# SolderingStation_Processor.net
KiCad netlist of a schematic drawn in Altium Designer
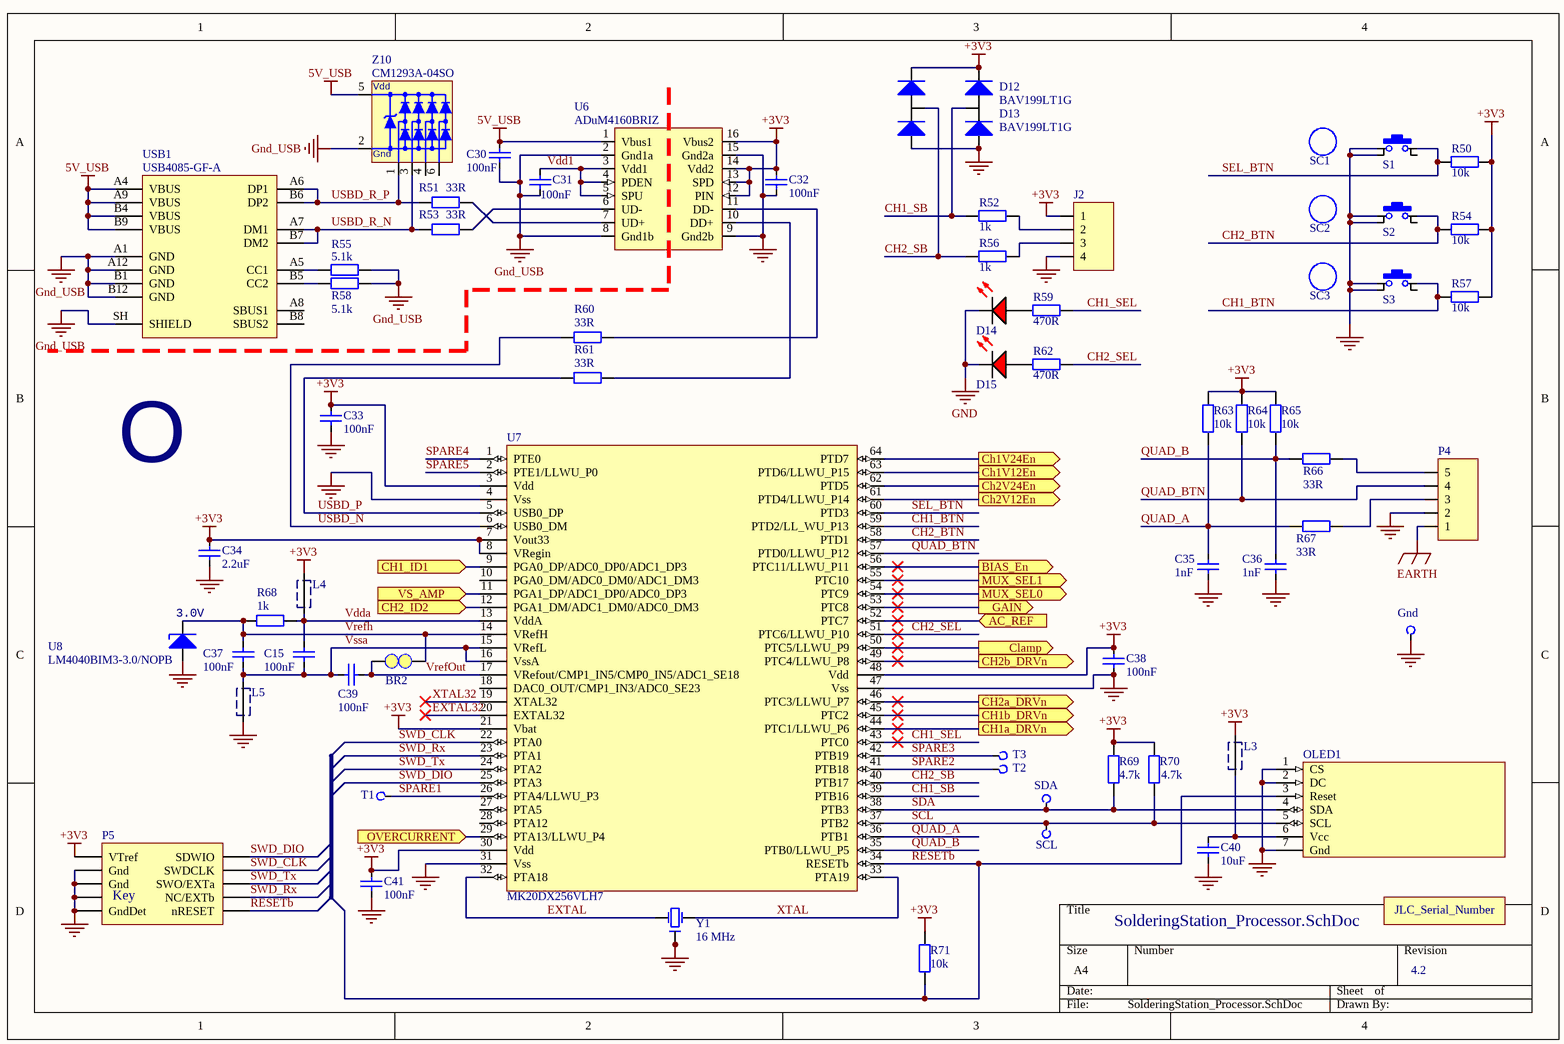
[diagram p0: SolderingStation_Processor.SchDoc]

(export (version "E")
  (design (tool "Eeschema 10.0.6"))
  (components
    (comp (ref "BR2")
      (value "Solder Bridge (Open)")
      (footprint "SolderBridge(Open)")
      (description "Solder bridge")
      (libsource (lib "MyLibrary") (part "SolderBridge(Open)"))
    )
    (comp (ref "C15")
      (value "100nF")
      (footprint "CCNP1608-0603_N")
      (description "Capacitor non-polar SMT 0603")
      (fields
        (field (name "MANUFACTURER") "Generic Components")
        (field (name "PUBLISHER") "Altium Hobart Technology Centre")
      )
      (libsource (lib "MyLibrary") (part "Cap_CCNP_0603_100nF"))
    )
    (comp (ref "C30")
      (value "100nF")
      (footprint "CCNP1608-0603_N")
      (description "Capacitor non-polar SMT 0603")
      (fields
        (field (name "MANUFACTURER") "Generic Components")
        (field (name "PUBLISHER") "Altium Hobart Technology Centre")
      )
      (libsource (lib "MyLibrary") (part "Cap_CCNP_0603_100nF"))
    )
    (comp (ref "C31")
      (value "100nF")
      (footprint "CCNP1608-0603_N")
      (description "Capacitor non-polar SMT 0603")
      (fields
        (field (name "MANUFACTURER") "Generic Components")
        (field (name "PUBLISHER") "Altium Hobart Technology Centre")
      )
      (libsource (lib "MyLibrary") (part "Cap_CCNP_0603_100nF"))
    )
    (comp (ref "C32")
      (value "100nF")
      (footprint "CCNP1608-0603_N")
      (description "Capacitor non-polar SMT 0603")
      (fields
        (field (name "MANUFACTURER") "Generic Components")
        (field (name "PUBLISHER") "Altium Hobart Technology Centre")
      )
      (libsource (lib "MyLibrary") (part "Cap_CCNP_0603_100nF"))
    )
    (comp (ref "C33")
      (value "100nF")
      (footprint "CCNP1608-0603_N")
      (description "Capacitor non-polar SMT 0603")
      (fields
        (field (name "MANUFACTURER") "Generic Components")
        (field (name "PUBLISHER") "Altium Hobart Technology Centre")
      )
      (libsource (lib "MyLibrary") (part "Cap_CCNP_0603_100nF"))
    )
    (comp (ref "C34")
      (value "2.2uF")
      (footprint "CCNP1608-0603_N")
      (description "Capacitor non-polar SMT 0603")
      (fields
        (field (name "MANUFACTURER") "Generic Components")
        (field (name "PUBLISHER") "Altium Hobart Technology Centre")
      )
      (libsource (lib "MyLibrary") (part "Cap_CCNP_0603_2u2F"))
    )
    (comp (ref "C35")
      (value "1nF")
      (footprint "CCNP1608-0603_N")
      (description "Capacitor non-polar SMT 0603")
      (fields
        (field (name "MANUFACTURER") "Generic Components")
        (field (name "PUBLISHER") "Altium Hobart Technology Centre")
      )
      (libsource (lib "MyLibrary") (part "Cap_CCNP_0603_1nF"))
    )
    (comp (ref "C36")
      (value "1nF")
      (footprint "CCNP1608-0603_N")
      (description "Capacitor non-polar SMT 0603")
      (fields
        (field (name "MANUFACTURER") "Generic Components")
        (field (name "PUBLISHER") "Altium Hobart Technology Centre")
      )
      (libsource (lib "MyLibrary") (part "Cap_CCNP_0603_1nF"))
    )
    (comp (ref "C37")
      (value "100nF")
      (footprint "CCNP1608-0603_N")
      (description "Capacitor non-polar SMT 0603")
      (fields
        (field (name "MANUFACTURER") "Generic Components")
        (field (name "PUBLISHER") "Altium Hobart Technology Centre")
      )
      (libsource (lib "MyLibrary") (part "Cap_CCNP_0603_100nF"))
    )
    (comp (ref "C38")
      (value "100nF")
      (footprint "CCNP1608-0603_N")
      (description "Capacitor non-polar SMT 0603")
      (fields
        (field (name "MANUFACTURER") "Generic Components")
        (field (name "PUBLISHER") "Altium Hobart Technology Centre")
      )
      (libsource (lib "MyLibrary") (part "Cap_CCNP_0603_100nF"))
    )
    (comp (ref "C39")
      (value "100nF")
      (footprint "CCNP1608-0603_N")
      (description "Capacitor non-polar SMT 0603")
      (fields
        (field (name "MANUFACTURER") "Generic Components")
        (field (name "PUBLISHER") "Altium Hobart Technology Centre")
      )
      (libsource (lib "MyLibrary") (part "Cap_CCNP_0603_100nF"))
    )
    (comp (ref "C40")
      (value "10uF")
      (footprint "CCNP2012-0805")
      (description "Capacitor non-polar SMT 0805")
      (fields
        (field (name "MANUFACTURER") "Generic Components")
        (field (name "PUBLISHER") "Altium Hobart Technology Centre")
      )
      (libsource (lib "MyLibrary") (part "Cap_CCNP_0805_10uF"))
    )
    (comp (ref "C41")
      (value "100nF")
      (footprint "CCNP1608-0603_N")
      (description "Capacitor non-polar SMT 0603")
      (fields
        (field (name "MANUFACTURER") "Generic Components")
        (field (name "PUBLISHER") "Altium Hobart Technology Centre")
      )
      (libsource (lib "MyLibrary") (part "Cap_CCNP_0603_100nF"))
    )
    (comp (ref "D12")
      (value "BAV199LT1G")
      (footprint "SOT23_M")
      (description "Dual Series low-leakage switching diodes, 3-Pin SOT-23")
      (libsource (lib "MySchLib") (part "BAV199LT1G"))
    )
    (comp (ref "D13")
      (value "BAV199LT1G")
      (footprint "SOT23_M")
      (description "Dual Series low-leakage switching diodes, 3-Pin SOT-23")
      (libsource (lib "MySchLib") (part "BAV199LT1G"))
    )
    (comp (ref "D14")
      (value "LED")
      (footprint "LED3MM-RED - 10mm Proud")
      (description "3mm Red LED")
      (fields (field (name "MANUFACTURER") "Generic Components") (field (name "PUBLISHER") "Altium Limited"))
      (libsource (lib "MySchLib") (part "LED_3MM_RED"))
    )
    (comp (ref "D15")
      (value "LED")
      (footprint "LED3MM-RED - 10mm Proud")
      (description "3mm Red LED")
      (fields (field (name "MANUFACTURER") "Generic Components") (field (name "PUBLISHER") "Altium Limited"))
      (libsource (lib "MySchLib") (part "LED_3MM_RED"))
    )
    (comp (ref "Gnd")
      (value "Gnd")
      (footprint "PCBPIN - 0.9mm")
      (description "Test Point")
      (libsource (lib "MySchLib") (part "TP"))
    )
    (comp (ref "J2")
      (value "JST XH Connector, 4-Pin")
      (footprint "jst-b4b-xh-ax")
      (fields (field (name "PUBLISHER") "Altium Limited"))
      (libsource (lib "MyLibrary") (part "JST-B4B-XH-A"))
    )
    (comp (ref "JLC_Serial_Number1")
      (value "JLC_Serial_Number")
      (footprint "JLC_Serial_Number")
      (libsource (lib "MyLibrary") (part "JLC_Serial_Number"))
    )
    (comp (ref "L3")
      (value "Ferrite Bead 600R@100MHz")
      (footprint "FB2012-0805")
      (description "Ferrite Bead 600Ω @ 100MHz 1 500mA 300mΩ 0805")
      (libsource (lib "MySchLib") (part "Ferrite Bead 0805 600R"))
    )
    (comp (ref "L4")
      (value "Ferrite Bead 600R@100MHz")
      (footprint "FB1608-0603")
      (description "Ferrite Bead 600Ω @ 100MHz 1 200mA 450mΩ 0603")
      (libsource (lib "MySchLib") (part "Ferrite Bead 0603 600R"))
    )
    (comp (ref "L5")
      (value "Ferrite Bead 600R@100MHz")
      (footprint "FB1608-0603")
      (description "Ferrite Bead 600Ω @ 100MHz 1 200mA 450mΩ 0603")
      (libsource (lib "MySchLib") (part "Ferrite Bead 0603 600R"))
    )
    (comp (ref "Logo1")
      (value "OSHW Logo")
      (footprint "OSHW")
      (libsource (lib "MyLibrary") (part "OSHW Logo"))
    )
    (comp (ref "OLED1")
      (value "OLED_Display")
      (footprint "OLED_Display_128x64_2.4inch - no mounting holes")
      (description "OLED Display 128x64 pixels, 2.4inch")
      (libsource (lib "MySchLib") (part "OLED_Display_128x64_2.4inch"))
    )
    (comp (ref "P4")
      (value "Header, 5-Pin")
      (footprint "HDR1X5S")
      (fields (field (name "PUBLISHER") "Altium Limited"))
      (libsource (lib "MyLibrary") (part "Header 1x5"))
    )
    (comp (ref "P5")
      (value "SWD Connector 2x5-Pin")
      (footprint "SWD-2x5-Jig-Header")
      (fields (field (name "PUBLISHER") "Altium Limited"))
      (libsource (lib "MySchLib") (part "SWD2X5_JIG"))
    )
    (comp (ref "R50")
      (value "10k")
      (footprint "CR1608-0603_N")
      (description "Resistor SMT 0603")
      (fields
        (field (name "MANUFACTURER") "Generic Components")
        (field (name "PUBLISHER") "Altium Hobart Technology Centre")
      )
      (libsource (lib "MyLibrary") (part "Res_CR0603_10k"))
    )
    (comp (ref "R51")
      (value "33R")
      (footprint "CR1608-0603_N")
      (description "Resistor SMT 0603")
      (fields
        (field (name "MANUFACTURER") "Generic Components")
        (field (name "PUBLISHER") "Altium Hobart Technology Centre")
      )
      (libsource (lib "MyLibrary") (part "Res_CR0603_33R"))
    )
    (comp (ref "R52")
      (value "1k")
      (footprint "CR1608-0603_N")
      (description "Resistor SMT 0603")
      (fields
        (field (name "MANUFACTURER") "Generic Components")
        (field (name "PUBLISHER") "Altium Hobart Technology Centre")
      )
      (libsource (lib "") (part "Res_CR0603_1k_1"))
    )
    (comp (ref "R53")
      (value "33R")
      (footprint "CR1608-0603_N")
      (description "Resistor SMT 0603")
      (fields
        (field (name "MANUFACTURER") "Generic Components")
        (field (name "PUBLISHER") "Altium Hobart Technology Centre")
      )
      (libsource (lib "MyLibrary") (part "Res_CR0603_33R"))
    )
    (comp (ref "R54")
      (value "10k")
      (footprint "CR1608-0603_N")
      (description "Resistor SMT 0603")
      (fields
        (field (name "MANUFACTURER") "Generic Components")
        (field (name "PUBLISHER") "Altium Hobart Technology Centre")
      )
      (libsource (lib "MyLibrary") (part "Res_CR0603_10k"))
    )
    (comp (ref "R55")
      (value "5.1k")
      (footprint "CR1608-0603_N")
      (description "Resistor SMT 0603")
      (fields
        (field (name "MANUFACTURER") "Generic Components")
        (field (name "PUBLISHER") "Altium Hobart Technology Centre")
      )
      (libsource (lib "MyLibrary") (part "Res_CR0603_5k1"))
    )
    (comp (ref "R56")
      (value "1k")
      (footprint "CR1608-0603_N")
      (description "Resistor SMT 0603")
      (fields
        (field (name "MANUFACTURER") "Generic Components")
        (field (name "PUBLISHER") "Altium Hobart Technology Centre")
      )
      (libsource (lib "") (part "Res_CR0603_1k_1"))
    )
    (comp (ref "R57")
      (value "10k")
      (footprint "CR1608-0603_N")
      (description "Resistor SMT 0603")
      (fields
        (field (name "MANUFACTURER") "Generic Components")
        (field (name "PUBLISHER") "Altium Hobart Technology Centre")
      )
      (libsource (lib "MyLibrary") (part "Res_CR0603_10k"))
    )
    (comp (ref "R58")
      (value "5.1k")
      (footprint "CR1608-0603_N")
      (description "Resistor SMT 0603")
      (fields
        (field (name "MANUFACTURER") "Generic Components")
        (field (name "PUBLISHER") "Altium Hobart Technology Centre")
      )
      (libsource (lib "MyLibrary") (part "Res_CR0603_5k1"))
    )
    (comp (ref "R59")
      (value "470R")
      (footprint "CR1608-0603_N")
      (description "Resistor SMT 0603")
      (fields
        (field (name "MANUFACTURER") "Generic Components")
        (field (name "PUBLISHER") "Altium Hobart Technology Centre")
      )
      (libsource (lib "MyLibrary") (part "Res_CR0603_470R"))
    )
    (comp (ref "R60")
      (value "33R")
      (footprint "CR1608-0603_N")
      (description "Resistor SMT 0603")
      (fields
        (field (name "MANUFACTURER") "Generic Components")
        (field (name "PUBLISHER") "Altium Hobart Technology Centre")
      )
      (libsource (lib "MyLibrary") (part "Res_CR0603_33R"))
    )
    (comp (ref "R61")
      (value "33R")
      (footprint "CR1608-0603_N")
      (description "Resistor SMT 0603")
      (fields
        (field (name "MANUFACTURER") "Generic Components")
        (field (name "PUBLISHER") "Altium Hobart Technology Centre")
      )
      (libsource (lib "MyLibrary") (part "Res_CR0603_33R"))
    )
    (comp (ref "R62")
      (value "470R")
      (footprint "CR1608-0603_N")
      (description "Resistor SMT 0603")
      (fields
        (field (name "MANUFACTURER") "Generic Components")
        (field (name "PUBLISHER") "Altium Hobart Technology Centre")
      )
      (libsource (lib "") (part "Res_CR0603_470R_1"))
    )
    (comp (ref "R63")
      (value "10k")
      (footprint "CR1608-0603_N")
      (description "Resistor SMT 0603")
      (fields
        (field (name "MANUFACTURER") "Generic Components")
        (field (name "PUBLISHER") "Altium Hobart Technology Centre")
      )
      (libsource (lib "") (part "Res_CR0603_10k_1"))
    )
    (comp (ref "R64")
      (value "10k")
      (footprint "CR1608-0603_N")
      (description "Resistor SMT 0603")
      (fields
        (field (name "MANUFACTURER") "Generic Components")
        (field (name "PUBLISHER") "Altium Hobart Technology Centre")
      )
      (libsource (lib "") (part "Res_CR0603_10k_1"))
    )
    (comp (ref "R65")
      (value "10k")
      (footprint "CR1608-0603_N")
      (description "Resistor SMT 0603")
      (fields
        (field (name "MANUFACTURER") "Generic Components")
        (field (name "PUBLISHER") "Altium Hobart Technology Centre")
      )
      (libsource (lib "") (part "Res_CR0603_10k_1"))
    )
    (comp (ref "R66")
      (value "33R")
      (footprint "CR1608-0603_N")
      (description "Resistor SMT 0603")
      (fields
        (field (name "MANUFACTURER") "Generic Components")
        (field (name "PUBLISHER") "Altium Hobart Technology Centre")
      )
      (libsource (lib "MyLibrary") (part "Res_CR0603_33R"))
    )
    (comp (ref "R67")
      (value "33R")
      (footprint "CR1608-0603_N")
      (description "Resistor SMT 0603")
      (fields
        (field (name "MANUFACTURER") "Generic Components")
        (field (name "PUBLISHER") "Altium Hobart Technology Centre")
      )
      (libsource (lib "MyLibrary") (part "Res_CR0603_33R"))
    )
    (comp (ref "R68")
      (value "1k")
      (footprint "CR1608-0603_N")
      (description "Resistor SMT 0603")
      (fields
        (field (name "MANUFACTURER") "Generic Components")
        (field (name "PUBLISHER") "Altium Hobart Technology Centre")
      )
      (libsource (lib "MyLibrary") (part "Res_CR0603_1k"))
    )
    (comp (ref "R69")
      (value "4.7k")
      (footprint "CR1608-0603_N")
      (description "Resistor SMT 0603")
      (fields
        (field (name "MANUFACTURER") "Generic Components")
        (field (name "PUBLISHER") "Altium Hobart Technology Centre")
      )
      (libsource (lib "MyLibrary") (part "Res_CR0603_4k7"))
    )
    (comp (ref "R70")
      (value "4.7k")
      (footprint "CR1608-0603_N")
      (description "Resistor SMT 0603")
      (fields
        (field (name "MANUFACTURER") "Generic Components")
        (field (name "PUBLISHER") "Altium Hobart Technology Centre")
      )
      (libsource (lib "MyLibrary") (part "Res_CR0603_4k7"))
    )
    (comp (ref "R71")
      (value "10k")
      (footprint "CR1608-0603_N")
      (description "Resistor SMT 0603")
      (fields
        (field (name "MANUFACTURER") "Generic Components")
        (field (name "PUBLISHER") "Altium Hobart Technology Centre")
      )
      (libsource (lib "") (part "Res_CR0603_10k_1"))
    )
    (comp (ref "S1")
      (value "SW_PB-B3F1052")
      (footprint "SW_MIN_PB-B3F1052")
      (description "Switch miniature push-button")
      (fields (field (name "MANUFACTURER") "Generic Components") (field (name "PUBLISHER") "Altium Limited"))
      (libsource (lib "MySchLib") (part "SW_PB-B3F1052"))
    )
    (comp (ref "S2")
      (value "SW_PB-B3F1052")
      (footprint "SW_MIN_PB-B3F1052")
      (description "Switch miniature push-button")
      (fields (field (name "MANUFACTURER") "Generic Components") (field (name "PUBLISHER") "Altium Limited"))
      (libsource (lib "MySchLib") (part "SW_PB-B3F1052"))
    )
    (comp (ref "S3")
      (value "SW_PB-B3F1052")
      (footprint "SW_MIN_PB-B3F1052")
      (description "Switch miniature push-button")
      (fields (field (name "MANUFACTURER") "Generic Components") (field (name "PUBLISHER") "Altium Limited"))
      (libsource (lib "MySchLib") (part "SW_PB-B3F1052"))
    )
    (comp (ref "SC1")
      (value "B32-2010")
      (footprint "SW-CAP-B32-2010")
      (description "Switch Cap")
      (libsource (lib "MySchLib") (part "Switch-Cap - B32-2010"))
    )
    (comp (ref "SC2")
      (value "B32-2010")
      (footprint "SW-CAP-B32-2010")
      (description "Switch Cap")
      (libsource (lib "MySchLib") (part "Switch-Cap - B32-2010"))
    )
    (comp (ref "SC3")
      (value "B32-2010")
      (footprint "SW-CAP-B32-2010")
      (description "Switch Cap")
      (libsource (lib "MySchLib") (part "Switch-Cap - B32-2010"))
    )
    (comp (ref "SCL")
      (value "SCL")
      (footprint "PCBPIN - 0.9mm")
      (description "Test Point")
      (libsource (lib "MySchLib") (part "TP"))
    )
    (comp (ref "SDA")
      (value "SDA")
      (footprint "PCBPIN - 0.9mm")
      (description "Test Point")
      (libsource (lib "MySchLib") (part "TP"))
    )
    (comp (ref "T1")
      (value "PTA4")
      (footprint "PCBPIN - 0.9mm")
      (description "Test Point")
      (libsource (lib "MySchLib") (part "TP"))
    )
    (comp (ref "T2")
      (value "PTB18")
      (footprint "PCBPIN - 0.9mm")
      (description "Test Point")
      (libsource (lib "MySchLib") (part "TP"))
    )
    (comp (ref "T3")
      (value "PTB19")
      (footprint "PCBPIN - 0.9mm")
      (description "Test Point")
      (libsource (lib "MySchLib") (part "TP"))
    )
    (comp (ref "U6")
      (value "ADuM4160BRIZ")
      (footprint "SOIC127P1030-16M")
      (description "Full/Low Speed 5 kV USB Digital Isolator")
      (libsource (lib "MySchLib") (part "ADuM4160BRIZ"))
    )
    (comp (ref "U7")
      (value "MK20DX256VLH7")
      (footprint "TSQFP50P1200X1200-64M")
      (description "Arm Cortex M4\r\nApplies to MK20DX64VLH7, MK20DX128VLH7, MK20DX256VLH7")
      (libsource (lib "MyLibrary") (part "MK20DX256VLH7"))
    )
    (comp (ref "U8")
      (value "LM4040BIM3-3.0/NOPB")
      (footprint "SOT23_M")
      (description "IC 2.5V VREF SHUNT 0.2% SOT23-3")
      (libsource (lib "MySchLib") (part "LM4040BIM3-2.5/NOPB"))
    )
    (comp (ref "USB1")
      (value "USB4085-GF-A")
      (footprint "USB4085-GF-A")
      (description "USB-C, USB 2.0 Receptacle Connector 16 Position Through Hole, Right Angle")
      (fields (field (name "DIGIKEY PART NUMBER") "2073-USB4085-GF-ACT-ND"))
      (libsource (lib "MyLibrary") (part "USB4085-GF-A"))
    )
    (comp (ref "Y1")
      (value "16 MHz")
      (footprint "Crystal_SMD_3.2x2.5")
      (description "Crystal SMD 3.2 x 2.5 x 0.7 mm")
      (fields
        (field (name "MANUFACTURER") "Generic Components")
        (field (name "PUBLISHER") "Altium Hobart Technology Centre")
      )
      (libsource (lib "MyLibrary") (part "Crystal 16MHz"))
    )
    (comp (ref "Z10")
      (value "CM1293A-04SO")
      (footprint "SOT457_M - 180")
      (description "Ultra low capacitance quadruple rail-to-rail ESD protection")
      (libsource (lib "MySchLib") (part "CM1293A-04SO"))
    )
  )
  (nets
    (net (code "1") (name "+3V3") (class "Default")
      (node (ref "C32") (pin "2") (pinfunction "2_2") (pintype "passive"))
      (node (ref "C33") (pin "2") (pinfunction "2_2") (pintype "passive"))
      (node (ref "C34") (pin "2") (pinfunction "2_2") (pintype "passive"))
      (node (ref "C38") (pin "2") (pinfunction "2_2") (pintype "passive"))
      (node (ref "C41") (pin "2") (pinfunction "2_2") (pintype "passive"))
      (node (ref "D12") (pin "2") (pinfunction "A2_2") (pintype "passive"))
      (node (ref "D13") (pin "2") (pinfunction "A2_2") (pintype "passive"))
      (node (ref "J2") (pin "1") (pinfunction "1_1") (pintype "passive"))
      (node (ref "L3") (pin "1") (pinfunction "1_1") (pintype "passive"))
      (node (ref "L4") (pin "2") (pinfunction "2_2") (pintype "passive"))
      (node (ref "P5") (pin "1") (pinfunction "VTref_1") (pintype "passive"))
      (node (ref "R50") (pin "2") (pinfunction "2_2") (pintype "passive"))
      (node (ref "R54") (pin "2") (pinfunction "2_2") (pintype "passive"))
      (node (ref "R57") (pin "2") (pinfunction "2_2") (pintype "passive"))
      (node (ref "R63") (pin "2") (pinfunction "2_2") (pintype "passive"))
      (node (ref "R64") (pin "2") (pinfunction "2_2") (pintype "passive"))
      (node (ref "R65") (pin "2") (pinfunction "2_2") (pintype "passive"))
      (node (ref "R69") (pin "2") (pinfunction "2_2") (pintype "passive"))
      (node (ref "R70") (pin "2") (pinfunction "2_2") (pintype "passive"))
      (node (ref "R71") (pin "2") (pinfunction "2_2") (pintype "passive"))
      (node (ref "U6") (pin "12") (pinfunction "PIN_12") (pintype "input"))
      (node (ref "U6") (pin "13") (pinfunction "SPD_13") (pintype "input"))
      (node (ref "U6") (pin "14") (pinfunction "Vdd2_14") (pintype "power_in"))
      (node (ref "U6") (pin "16") (pinfunction "Vbus2_16") (pintype "power_in"))
      (node (ref "U7") (pin "21") (pinfunction "Vbat_21") (pintype "passive"))
      (node (ref "U7") (pin "3") (pinfunction "Vdd_3") (pintype "power_in"))
      (node (ref "U7") (pin "30") (pinfunction "Vdd_30") (pintype "power_in"))
      (node (ref "U7") (pin "48") (pinfunction "Vdd_48") (pintype "power_in"))
      (node (ref "U7") (pin "7") (pinfunction "Vout33_7") (pintype "power_in"))
      (node (ref "U7") (pin "8") (pinfunction "VRegin_8") (pintype "passive"))
    )
    (net (code "2") (name "/AC_REF") (class "Default")
      (node (ref "U7") (pin "52") (pinfunction "PTC7_52") (pintype "bidirectional"))
    )
    (net (code "3") (name "/BIAS_En") (class "Default")
      (node (ref "U7") (pin "56") (pinfunction "PTC11/LLWU_P11_56") (pintype "bidirectional"))
    )
    (net (code "4") (name "/CH1_BTN") (class "Default")
      (node (ref "R57") (pin "1") (pinfunction "1_1") (pintype "passive"))
      (node (ref "S3") (pin "2") (pinfunction "2_2") (pintype "passive"))
      (node (ref "U7") (pin "59") (pinfunction "PTD2/LL_WU_P13_59") (pintype "bidirectional"))
    )
    (net (code "5") (name "/CH1_ID1") (class "Default")
      (node (ref "U7") (pin "9") (pinfunction "PGA0_DP/ADC0_DP0/ADC1_DP3_9") (pintype "passive"))
    )
    (net (code "6") (name "/CH1_SB") (class "Default")
      (node (ref "D13") (pin "3") (pinfunction "K_3") (pintype "passive"))
      (node (ref "R52") (pin "1") (pinfunction "1_1") (pintype "passive"))
      (node (ref "U7") (pin "39") (pinfunction "PTB16_39") (pintype "bidirectional"))
    )
    (net (code "7") (name "/CH1_SEL") (class "Default")
      (node (ref "R59") (pin "1") (pinfunction "1_1") (pintype "passive"))
      (node (ref "U7") (pin "43") (pinfunction "PTC0_43") (pintype "bidirectional"))
    )
    (net (code "8") (name "/CH1a_DRVn") (class "Default")
      (node (ref "U7") (pin "44") (pinfunction "PTC1/LLWU_P6_44") (pintype "bidirectional"))
    )
    (net (code "9") (name "/CH1b_DRVn") (class "Default")
      (node (ref "U7") (pin "45") (pinfunction "PTC2_45") (pintype "bidirectional"))
    )
    (net (code "10") (name "/CH2_BTN") (class "Default")
      (node (ref "R54") (pin "1") (pinfunction "1_1") (pintype "passive"))
      (node (ref "S2") (pin "2") (pinfunction "2_2") (pintype "passive"))
      (node (ref "U7") (pin "58") (pinfunction "PTD1_58") (pintype "bidirectional"))
    )
    (net (code "11") (name "/CH2_ID2") (class "Default")
      (node (ref "U7") (pin "12") (pinfunction "PGA1_DM/ADC1_DM0/ADC0_DM3_12") (pintype "passive"))
    )
    (net (code "12") (name "/CH2_SB") (class "Default")
      (node (ref "D12") (pin "3") (pinfunction "K_3") (pintype "passive"))
      (node (ref "R56") (pin "1") (pinfunction "1_1") (pintype "passive"))
      (node (ref "U7") (pin "40") (pinfunction "PTB17_40") (pintype "bidirectional"))
    )
    (net (code "13") (name "/CH2_SEL") (class "Default")
      (node (ref "R62") (pin "2") (pinfunction "2_2") (pintype "passive"))
      (node (ref "U7") (pin "51") (pinfunction "PTC6/LLWU_P10_51") (pintype "bidirectional"))
    )
    (net (code "14") (name "/CH2a_DRVn") (class "Default")
      (node (ref "U7") (pin "46") (pinfunction "PTC3/LLWU_P7_46") (pintype "bidirectional"))
    )
    (net (code "15") (name "/CH2b_DRVn") (class "Default")
      (node (ref "U7") (pin "49") (pinfunction "PTC4/LLWU_P8_49") (pintype "bidirectional"))
    )
    (net (code "16") (name "/Ch1V12En") (class "Default")
      (node (ref "U7") (pin "63") (pinfunction "PTD6/LLWU_P15_63") (pintype "bidirectional"))
    )
    (net (code "17") (name "/Ch1V24En") (class "Default")
      (node (ref "U7") (pin "64") (pinfunction "PTD7_64") (pintype "bidirectional"))
    )
    (net (code "18") (name "/Ch2V12En") (class "Default")
      (node (ref "U7") (pin "61") (pinfunction "PTD4/LLWU_P14_61") (pintype "bidirectional"))
    )
    (net (code "19") (name "/Ch2V24En") (class "Default")
      (node (ref "U7") (pin "62") (pinfunction "PTD5_62") (pintype "bidirectional"))
    )
    (net (code "20") (name "/Clamp") (class "Default")
      (node (ref "U7") (pin "50") (pinfunction "PTC5/LLWU_P9_50") (pintype "bidirectional"))
    )
    (net (code "21") (name "/EXTAL") (class "Default")
      (node (ref "U7") (pin "32") (pinfunction "PTA18_32") (pintype "bidirectional"))
      (node (ref "Y1") (pin "3") (pinfunction "OSC2_3") (pintype "passive"))
    )
    (net (code "22") (name "/EXTAL32") (class "Default")
      (node (ref "U7") (pin "20") (pinfunction "EXTAL32_20") (pintype "passive+no_connect"))
    )
    (net (code "23") (name "/GAIN") (class "Default")
      (node (ref "U7") (pin "53") (pinfunction "PTC8_53") (pintype "bidirectional"))
    )
    (net (code "24") (name "/MUX_SEL0") (class "Default")
      (node (ref "U7") (pin "54") (pinfunction "PTC9_54") (pintype "bidirectional"))
    )
    (net (code "25") (name "/MUX_SEL1") (class "Default")
      (node (ref "U7") (pin "55") (pinfunction "PTC10_55") (pintype "bidirectional"))
    )
    (net (code "26") (name "/OVERCURRENT") (class "Default")
      (node (ref "U7") (pin "29") (pinfunction "PTA13/LLWU_P4_29") (pintype "bidirectional"))
    )
    (net (code "27") (name "/QUAD_A") (class "Default")
      (node (ref "C35") (pin "2") (pinfunction "2_2") (pintype "passive"))
      (node (ref "R63") (pin "1") (pinfunction "1_1") (pintype "passive"))
      (node (ref "R67") (pin "2") (pinfunction "2_2") (pintype "passive"))
      (node (ref "U7") (pin "36") (pinfunction "PTB1_36") (pintype "bidirectional"))
    )
    (net (code "28") (name "/QUAD_B") (class "Default")
      (node (ref "C36") (pin "2") (pinfunction "2_2") (pintype "passive"))
      (node (ref "R65") (pin "1") (pinfunction "1_1") (pintype "passive"))
      (node (ref "R66") (pin "2") (pinfunction "2_2") (pintype "passive"))
      (node (ref "U7") (pin "35") (pinfunction "PTB0/LLWU_P5_35") (pintype "bidirectional"))
    )
    (net (code "29") (name "/QUAD_BTN") (class "Default")
      (node (ref "P4") (pin "4") (pinfunction "4_4") (pintype "passive"))
      (node (ref "R64") (pin "1") (pinfunction "1_1") (pintype "passive"))
      (node (ref "U7") (pin "57") (pinfunction "PTD0/LLWU_P12_57") (pintype "bidirectional"))
    )
    (net (code "30") (name "/RESETb") (class "Default")
      (node (ref "OLED1") (pin "3") (pinfunction "Reset_3") (pintype "input"))
      (node (ref "P5") (pin "10") (pinfunction "nRESET_10") (pintype "passive"))
      (node (ref "R71") (pin "1") (pinfunction "1_1") (pintype "passive"))
      (node (ref "U7") (pin "34") (pinfunction "RESETb_34") (pintype "bidirectional"))
    )
    (net (code "31") (name "/SCL") (class "Default")
      (node (ref "OLED1") (pin "5") (pinfunction "SCL_5") (pintype "bidirectional"))
      (node (ref "R70") (pin "1") (pinfunction "1_1") (pintype "passive"))
      (node (ref "SCL") (pin "1") (pinfunction "TP_1") (pintype "passive"))
      (node (ref "U7") (pin "37") (pinfunction "PTB2_37") (pintype "bidirectional"))
    )
    (net (code "32") (name "/SDA") (class "Default")
      (node (ref "OLED1") (pin "4") (pinfunction "SDA_4") (pintype "bidirectional"))
      (node (ref "R69") (pin "1") (pinfunction "1_1") (pintype "passive"))
      (node (ref "SDA") (pin "1") (pinfunction "TP_1") (pintype "passive"))
      (node (ref "U7") (pin "38") (pinfunction "PTB3_38") (pintype "bidirectional"))
    )
    (net (code "33") (name "/SEL_BTN") (class "Default")
      (node (ref "R50") (pin "1") (pinfunction "1_1") (pintype "passive"))
      (node (ref "S1") (pin "2") (pinfunction "2_2") (pintype "passive"))
      (node (ref "U7") (pin "60") (pinfunction "PTD3_60") (pintype "bidirectional"))
    )
    (net (code "34") (name "/SPARE1") (class "Default")
      (node (ref "T1") (pin "1") (pinfunction "TP_1") (pintype "passive"))
      (node (ref "U7") (pin "26") (pinfunction "PTA4/LLWU_P3_26") (pintype "bidirectional"))
    )
    (net (code "35") (name "/SPARE2") (class "Default")
      (node (ref "T2") (pin "1") (pinfunction "TP_1") (pintype "passive"))
      (node (ref "U7") (pin "41") (pinfunction "PTB18_41") (pintype "bidirectional"))
    )
    (net (code "36") (name "/SPARE3") (class "Default")
      (node (ref "T3") (pin "1") (pinfunction "TP_1") (pintype "passive"))
      (node (ref "U7") (pin "42") (pinfunction "PTB19_42") (pintype "bidirectional"))
    )
    (net (code "37") (name "/SPARE4") (class "Default")
      (node (ref "U7") (pin "1") (pinfunction "PTE0_1") (pintype "bidirectional"))
    )
    (net (code "38") (name "/SPARE5") (class "Default")
      (node (ref "U7") (pin "2") (pinfunction "PTE1/LLWU_P0_2") (pintype "bidirectional"))
    )
    (net (code "39") (name "/SWD_CLK") (class "Default")
      (node (ref "P5") (pin "4") (pinfunction "SWDCLK_4") (pintype "passive"))
      (node (ref "U7") (pin "22") (pinfunction "PTA0_22") (pintype "bidirectional"))
    )
    (net (code "40") (name "/SWD_DIO") (class "Default")
      (node (ref "P5") (pin "2") (pinfunction "SDWIO_2") (pintype "passive"))
      (node (ref "U7") (pin "25") (pinfunction "PTA3_25") (pintype "bidirectional"))
    )
    (net (code "41") (name "/SWD_Rx") (class "Default")
      (node (ref "P5") (pin "8") (pinfunction "NC/EXTb_8") (pintype "passive"))
      (node (ref "U7") (pin "23") (pinfunction "PTA1_23") (pintype "bidirectional"))
    )
    (net (code "42") (name "/SWD_Tx") (class "Default")
      (node (ref "P5") (pin "6") (pinfunction "SWO/EXTa_6") (pintype "passive"))
      (node (ref "U7") (pin "24") (pinfunction "PTA2_24") (pintype "bidirectional"))
    )
    (net (code "43") (name "/USBD_N") (class "Default")
      (node (ref "R60") (pin "2") (pinfunction "2_2") (pintype "passive"))
      (node (ref "U7") (pin "6") (pinfunction "USB0_DM_6") (pintype "bidirectional"))
    )
    (net (code "44") (name "/USBD_P") (class "Default")
      (node (ref "R61") (pin "2") (pinfunction "2_2") (pintype "passive"))
      (node (ref "U7") (pin "5") (pinfunction "USB0_DP_5") (pintype "bidirectional"))
    )
    (net (code "45") (name "/USBD_R_N") (class "Default")
      (node (ref "R53") (pin "2") (pinfunction "2_2") (pintype "passive"))
      (node (ref "USB1") (pin "A7") (pinfunction "DM1_A7") (pintype "passive"))
      (node (ref "USB1") (pin "B7") (pinfunction "DM2_B7") (pintype "passive"))
      (node (ref "Z10") (pin "3") (pintype "passive"))
    )
    (net (code "46") (name "/USBD_R_P") (class "Default")
      (node (ref "R51") (pin "2") (pinfunction "2_2") (pintype "passive"))
      (node (ref "USB1") (pin "A6") (pinfunction "DP1_A6") (pintype "passive"))
      (node (ref "USB1") (pin "B6") (pinfunction "DP2_B6") (pintype "passive"))
      (node (ref "Z10") (pin "1") (pintype "passive"))
    )
    (net (code "47") (name "/VS_AMP") (class "Default")
      (node (ref "U7") (pin "11") (pinfunction "PGA1_DP/ADC1_DP0/ADC0_DP3_11") (pintype "passive"))
    )
    (net (code "48") (name "/Vdd1") (class "Default")
      (node (ref "C31") (pin "2") (pinfunction "2_2") (pintype "passive"))
      (node (ref "U6") (pin "3") (pinfunction "Vdd1_3") (pintype "power_in"))
      (node (ref "U6") (pin "4") (pinfunction "PDEN_4") (pintype "input"))
      (node (ref "U6") (pin "5") (pinfunction "SPU_5") (pintype "input"))
    )
    (net (code "49") (name "/Vdda") (class "Default")
      (node (ref "C15") (pin "2") (pinfunction "2_2") (pintype "passive"))
      (node (ref "L4") (pin "1") (pinfunction "1_1") (pintype "passive"))
      (node (ref "R68") (pin "1") (pinfunction "1_1") (pintype "passive"))
      (node (ref "U7") (pin "13") (pinfunction "VddA_13") (pintype "power_in"))
    )
    (net (code "50") (name "/VrefOut") (class "Default")
      (node (ref "BR2") (pin "1") (pintype "passive"))
      (node (ref "C39") (pin "2") (pinfunction "2_2") (pintype "passive"))
      (node (ref "U7") (pin "17") (pinfunction "VRefout/CMP1_IN5/CMP0_IN5/ADC1_SE18_17") (pintype "passive"))
    )
    (net (code "51") (name "/Vrefh") (class "Default")
      (node (ref "BR2") (pin "2") (pintype "passive"))
      (node (ref "C37") (pin "2") (pinfunction "2_2") (pintype "passive"))
      (node (ref "R68") (pin "2") (pinfunction "2_2") (pintype "passive"))
      (node (ref "U7") (pin "14") (pinfunction "VRefH_14") (pintype "passive"))
      (node (ref "U8") (pin "1") (pinfunction "K_1") (pintype "passive"))
    )
    (net (code "52") (name "/Vssa") (class "Default")
      (node (ref "C15") (pin "1") (pinfunction "1_1") (pintype "passive"))
      (node (ref "C37") (pin "1") (pinfunction "1_1") (pintype "passive"))
      (node (ref "C39") (pin "1") (pinfunction "1_1") (pintype "passive"))
      (node (ref "L5") (pin "2") (pinfunction "2_2") (pintype "passive"))
      (node (ref "U7") (pin "15") (pinfunction "VRefL_15") (pintype "passive"))
      (node (ref "U7") (pin "16") (pinfunction "VssA_16") (pintype "power_in"))
    )
    (net (code "53") (name "/XTAL") (class "Default")
      (node (ref "U7") (pin "33") (pinfunction "PTA19_33") (pintype "bidirectional"))
      (node (ref "Y1") (pin "1") (pinfunction "OSC1_1") (pintype "passive"))
    )
    (net (code "54") (name "/XTAL32") (class "Default")
      (node (ref "U7") (pin "19") (pinfunction "XTAL32_19") (pintype "passive+no_connect"))
    )
    (net (code "55") (name "5V_USB") (class "Default")
      (node (ref "C30") (pin "2") (pinfunction "2_2") (pintype "passive"))
      (node (ref "U6") (pin "1") (pinfunction "Vbus1_1") (pintype "power_in"))
      (node (ref "USB1") (pin "A4") (pinfunction "VBUS_A4") (pintype "passive"))
      (node (ref "USB1") (pin "A9") (pinfunction "VBUS_A9") (pintype "passive"))
      (node (ref "USB1") (pin "B4") (pinfunction "VBUS_B4") (pintype "passive"))
      (node (ref "USB1") (pin "B9") (pinfunction "VBUS_B9") (pintype "passive"))
      (node (ref "Z10") (pin "5") (pinfunction "Vp_5") (pintype "passive"))
    )
    (net (code "56") (name "EARTH") (class "Default")
      (node (ref "P4") (pin "1") (pinfunction "1_1") (pintype "passive"))
    )
    (net (code "57") (name "GND") (class "Default")
      (node (ref "C32") (pin "1") (pinfunction "1_1") (pintype "passive"))
      (node (ref "C33") (pin "1") (pinfunction "1_1") (pintype "passive"))
      (node (ref "C34") (pin "1") (pinfunction "1_1") (pintype "passive"))
      (node (ref "C35") (pin "1") (pinfunction "1_1") (pintype "passive"))
      (node (ref "C36") (pin "1") (pinfunction "1_1") (pintype "passive"))
      (node (ref "C38") (pin "1") (pinfunction "1_1") (pintype "passive"))
      (node (ref "C40") (pin "1") (pinfunction "1_1") (pintype "passive"))
      (node (ref "C41") (pin "1") (pinfunction "1_1") (pintype "passive"))
      (node (ref "D12") (pin "1") (pinfunction "A1_1") (pintype "passive"))
      (node (ref "D13") (pin "1") (pinfunction "A1_1") (pintype "passive"))
      (node (ref "D14") (pin "K") (pinfunction "K_K") (pintype "passive"))
      (node (ref "D15") (pin "K") (pinfunction "K_K") (pintype "passive"))
      (node (ref "Gnd") (pin "1") (pinfunction "TP_1") (pintype "passive"))
      (node (ref "J2") (pin "4") (pinfunction "4_4") (pintype "passive"))
      (node (ref "L5") (pin "1") (pinfunction "1_1") (pintype "passive"))
      (node (ref "OLED1") (pin "1") (pinfunction "CS_1") (pintype "input"))
      (node (ref "OLED1") (pin "2") (pinfunction "DC_2") (pintype "input"))
      (node (ref "OLED1") (pin "7") (pinfunction "Gnd_7") (pintype "power_in"))
      (node (ref "P4") (pin "2") (pinfunction "2_2") (pintype "passive"))
      (node (ref "P5") (pin "0") (pinfunction "Pins_0") (pintype "power_in"))
      (node (ref "P5") (pin "3") (pinfunction "Gnd_3") (pintype "passive"))
      (node (ref "P5") (pin "5") (pinfunction "Gnd_5") (pintype "passive"))
      (node (ref "P5") (pin "9") (pinfunction "GndDet_9") (pintype "passive"))
      (node (ref "S1") (pin "1") (pinfunction "1_1") (pintype "passive"))
      (node (ref "S1") (pin "1b") (pinfunction "1b_1b") (pintype "passive"))
      (node (ref "S2") (pin "1") (pinfunction "1_1") (pintype "passive"))
      (node (ref "S2") (pin "1b") (pinfunction "1b_1b") (pintype "passive"))
      (node (ref "S3") (pin "1") (pinfunction "1_1") (pintype "passive"))
      (node (ref "S3") (pin "1b") (pinfunction "1b_1b") (pintype "passive"))
      (node (ref "U6") (pin "15") (pinfunction "Gnd2a_15") (pintype "power_in"))
      (node (ref "U6") (pin "9") (pinfunction "Gnd2b_9") (pintype "power_in"))
      (node (ref "U7") (pin "31") (pinfunction "Vss_31") (pintype "power_in"))
      (node (ref "U7") (pin "4") (pinfunction "Vss_4") (pintype "power_in"))
      (node (ref "U7") (pin "47") (pinfunction "Vss_47") (pintype "power_in"))
      (node (ref "U8") (pin "2") (pinfunction "A_2") (pintype "passive"))
      (node (ref "Y1") (pin "2") (pinfunction "Gnd_2") (pintype "passive"))
      (node (ref "Y1") (pin "4") (pinfunction "Gnd_4") (pintype "passive"))
    )
    (net (code "58") (name "Gnd_USB") (class "Default")
      (node (ref "C30") (pin "1") (pinfunction "1_1") (pintype "passive"))
      (node (ref "C31") (pin "1") (pinfunction "1_1") (pintype "passive"))
      (node (ref "R55") (pin "2") (pinfunction "2_2") (pintype "passive"))
      (node (ref "R58") (pin "2") (pinfunction "2_2") (pintype "passive"))
      (node (ref "U6") (pin "2") (pinfunction "Gnd1a_2") (pintype "power_in"))
      (node (ref "U6") (pin "8") (pinfunction "Gnd1b_8") (pintype "power_in"))
      (node (ref "USB1") (pin "A1") (pinfunction "GND_A1") (pintype "passive"))
      (node (ref "USB1") (pin "A12") (pinfunction "GND_A12") (pintype "passive"))
      (node (ref "USB1") (pin "B1") (pinfunction "GND_B1") (pintype "passive"))
      (node (ref "USB1") (pin "B12") (pinfunction "GND_B12") (pintype "passive"))
      (node (ref "USB1") (pin "SH") (pinfunction "SHIELD_SH") (pintype "passive"))
      (node (ref "Z10") (pin "2") (pinfunction "Vn_2") (pintype "passive"))
    )
    (net (code "59") (name "Net-(D14-PadA)") (class "Default")
      (node (ref "D14") (pin "A") (pinfunction "A_A") (pintype "passive"))
      (node (ref "R59") (pin "2") (pinfunction "2_2") (pintype "passive"))
    )
    (net (code "60") (name "Net-(D15-PadA)") (class "Default")
      (node (ref "D15") (pin "A") (pinfunction "A_A") (pintype "passive"))
      (node (ref "R62") (pin "1") (pinfunction "1_1") (pintype "passive"))
    )
    (net (code "61") (name "Net-(J2-Pad2)") (class "Default")
      (node (ref "J2") (pin "2") (pinfunction "2_2") (pintype "passive"))
      (node (ref "R52") (pin "2") (pinfunction "2_2") (pintype "passive"))
    )
    (net (code "62") (name "Net-(J2-Pad3)") (class "Default")
      (node (ref "J2") (pin "3") (pinfunction "3_3") (pintype "passive"))
      (node (ref "R56") (pin "2") (pinfunction "2_2") (pintype "passive"))
    )
    (net (code "63") (name "Net-(OLED1-Vcc)") (class "Default")
      (node (ref "C40") (pin "2") (pinfunction "2_2") (pintype "passive"))
      (node (ref "L3") (pin "2") (pinfunction "2_2") (pintype "passive"))
      (node (ref "OLED1") (pin "6") (pinfunction "Vcc_6") (pintype "power_in"))
    )
    (net (code "64") (name "Net-(P4-Pad3)") (class "Default")
      (node (ref "P4") (pin "3") (pinfunction "3_3") (pintype "passive"))
      (node (ref "R67") (pin "1") (pinfunction "1_1") (pintype "passive"))
    )
    (net (code "65") (name "Net-(P4-Pad5)") (class "Default")
      (node (ref "P4") (pin "5") (pinfunction "5_5") (pintype "passive"))
      (node (ref "R66") (pin "1") (pinfunction "1_1") (pintype "passive"))
    )
    (net (code "66") (name "Net-(U6-DD+)") (class "Default")
      (node (ref "R61") (pin "1") (pinfunction "1_1") (pintype "passive"))
      (node (ref "U6") (pin "10") (pinfunction "DD+_10") (pintype "bidirectional"))
    )
    (net (code "67") (name "Net-(U6-DD-)") (class "Default")
      (node (ref "R60") (pin "1") (pinfunction "1_1") (pintype "passive"))
      (node (ref "U6") (pin "11") (pinfunction "DD-_11") (pintype "bidirectional"))
    )
    (net (code "68") (name "Net-(U6-UD+)") (class "Default")
      (node (ref "R51") (pin "1") (pinfunction "1_1") (pintype "passive"))
      (node (ref "U6") (pin "7") (pinfunction "UD+_7") (pintype "bidirectional"))
    )
    (net (code "69") (name "Net-(U6-UD-)") (class "Default")
      (node (ref "R53") (pin "1") (pinfunction "1_1") (pintype "passive"))
      (node (ref "U6") (pin "6") (pinfunction "UD-_6") (pintype "bidirectional"))
    )
    (net (code "70") (name "Net-(USB1-CC1)") (class "Default")
      (node (ref "R55") (pin "1") (pinfunction "1_1") (pintype "passive"))
      (node (ref "USB1") (pin "A5") (pinfunction "CC1_A5") (pintype "passive"))
    )
    (net (code "71") (name "Net-(USB1-CC2)") (class "Default")
      (node (ref "R58") (pin "1") (pinfunction "1_1") (pintype "passive"))
      (node (ref "USB1") (pin "B5") (pinfunction "CC2_B5") (pintype "passive"))
    )
    (net (code "72") (name "unconnected-(S1-Pad2b)") (class "Default")
      (node (ref "S1") (pin "2b") (pinfunction "2b_2b") (pintype "passive"))
    )
    (net (code "73") (name "unconnected-(S2-Pad2b)") (class "Default")
      (node (ref "S2") (pin "2b") (pinfunction "2b_2b") (pintype "passive"))
    )
    (net (code "74") (name "unconnected-(S3-Pad2b)") (class "Default")
      (node (ref "S3") (pin "2b") (pinfunction "2b_2b") (pintype "passive"))
    )
    (net (code "75") (name "unconnected-(U7-DAC0_OUT{slash}CMP1_IN3{slash}ADC0_SE23-Pad18)") (class "Default")
      (node (ref "U7") (pin "18") (pinfunction "DAC0_OUT/CMP1_IN3/ADC0_SE23_18") (pintype "passive"))
    )
    (net (code "76") (name "unconnected-(U7-PGA0_DM{slash}ADC0_DM0{slash}ADC1_DM3-Pad10)") (class "Default")
      (node (ref "U7") (pin "10") (pinfunction "PGA0_DM/ADC0_DM0/ADC1_DM3_10") (pintype "passive"))
    )
    (net (code "77") (name "unconnected-(U7-PTA5-Pad27)") (class "Default")
      (node (ref "U7") (pin "27") (pinfunction "PTA5_27") (pintype "bidirectional"))
    )
    (net (code "78") (name "unconnected-(U7-PTA12-Pad28)") (class "Default")
      (node (ref "U7") (pin "28") (pinfunction "PTA12_28") (pintype "bidirectional"))
    )
    (net (code "79") (name "unconnected-(U8-NC-Pad3)") (class "Default")
      (node (ref "U8") (pin "3") (pinfunction "NC_3") (pintype "passive"))
    )
    (net (code "80") (name "unconnected-(USB1-SBUS1-PadA8)") (class "Default")
      (node (ref "USB1") (pin "A8") (pinfunction "SBUS1_A8") (pintype "passive"))
    )
    (net (code "81") (name "unconnected-(USB1-SBUS2-PadB8)") (class "Default")
      (node (ref "USB1") (pin "B8") (pinfunction "SBUS2_B8") (pintype "passive"))
    )
    (net (code "82") (name "unconnected-(Z10-Pad4)") (class "Default")
      (node (ref "Z10") (pin "4") (pintype "passive"))
    )
    (net (code "83") (name "unconnected-(Z10-Pad6)") (class "Default")
      (node (ref "Z10") (pin "6") (pintype "passive"))
    )
  )
)
